# INH_v4_01.net
KiCad netlist of a schematic drawn in Altium Designer
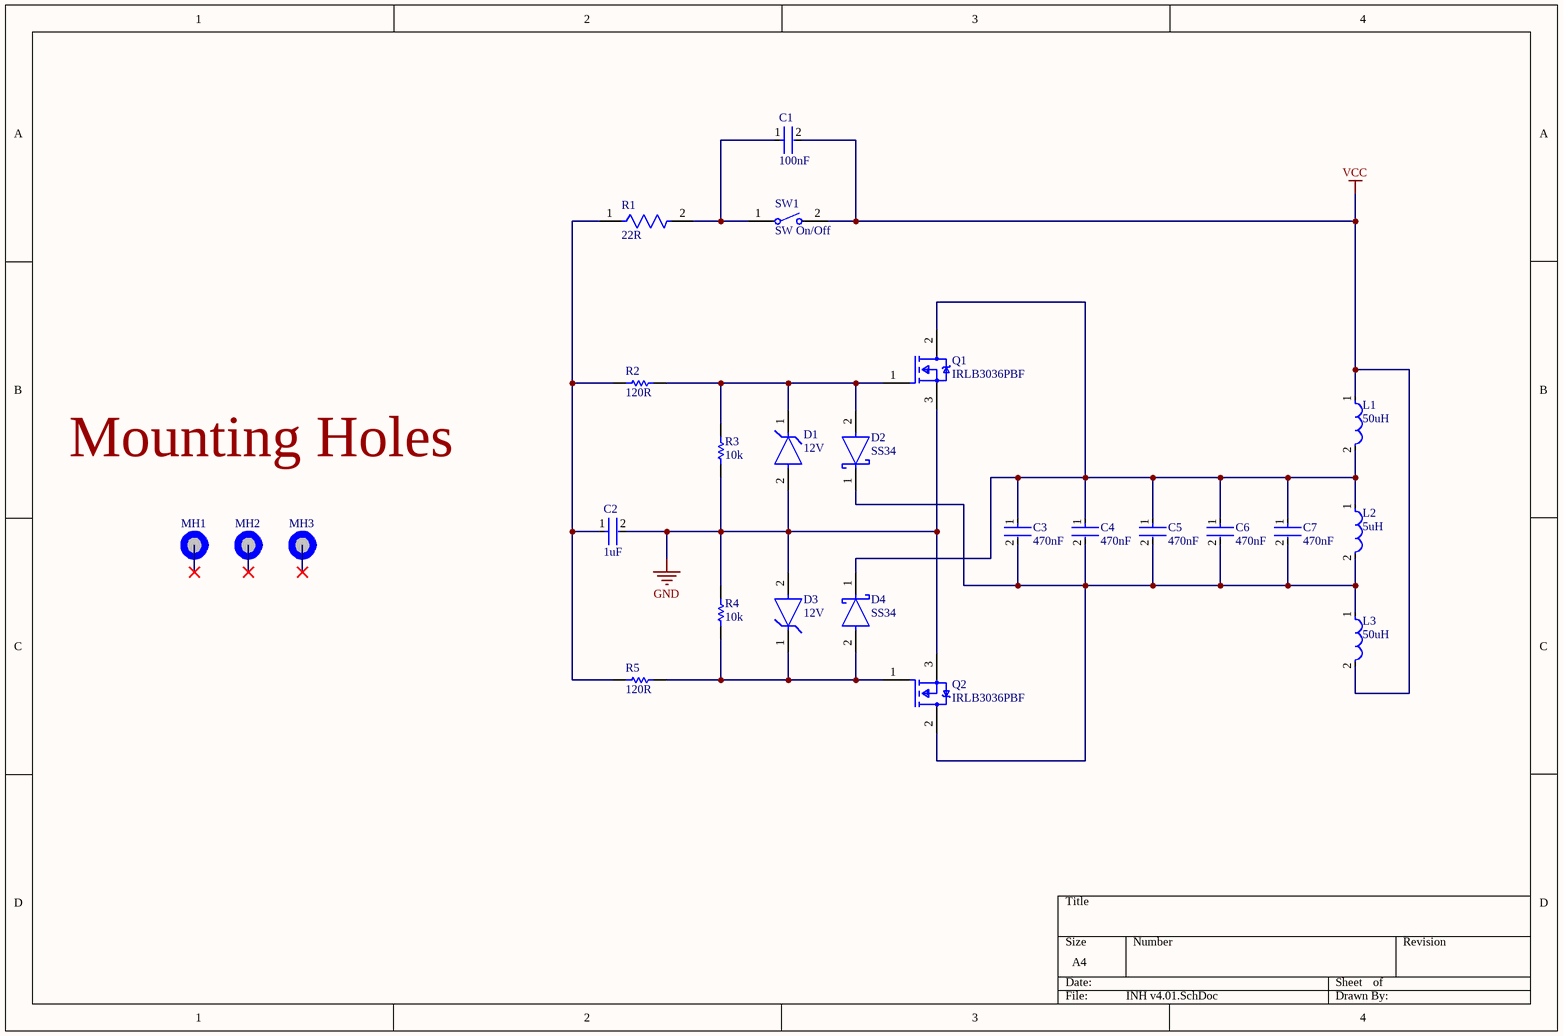
[diagram p0: INH v4.01.SchDoc]

(export (version "E")
  (design (tool "Eeschema 10.0.6"))
  (components
    (comp (ref "C1")
      (value "100nF")
      (footprint "1206 Capacitor")
      (libsource (lib "INH v4.01") (part "C 1206 100nF"))
    )
    (comp (ref "C2")
      (value "1uF")
      (footprint "1206 Capacitor")
      (description "Cap Ceramic 1uF 25V X7R ±20% SMD 1206 +125°C Embossed T/R")
      (fields (field (name "TOLERANCE") "20%"))
      (libsource (lib "INH v4.01") (part "C 1206 1uF"))
    )
    (comp (ref "C3")
      (value "470nF")
      (footprint "THT Capacitor P15mm (84x183mm)")
      (description "PP X2 Capacitor 470nF 275V")
      (libsource (lib "INH v4.01") (part "C 084x183 P15 470nF"))
    )
    (comp (ref "C4")
      (value "470nF")
      (footprint "THT Capacitor P15mm (84x183mm)")
      (description "PP X2 Capacitor 470nF 275V")
      (libsource (lib "INH v4.01") (part "C 084x183 P15 470nF"))
    )
    (comp (ref "C5")
      (value "470nF")
      (footprint "THT Capacitor P15mm (84x183mm)")
      (description "PP X2 Capacitor 470nF 275V")
      (libsource (lib "INH v4.01") (part "C 084x183 P15 470nF"))
    )
    (comp (ref "C6")
      (value "470nF")
      (footprint "THT Capacitor P15mm (84x183mm)")
      (description "PP X2 Capacitor 470nF 275V")
      (libsource (lib "INH v4.01") (part "C 084x183 P15 470nF"))
    )
    (comp (ref "C7")
      (value "470nF")
      (footprint "THT Capacitor P15mm (84x183mm)")
      (description "PP X2 Capacitor 470nF 275V")
      (libsource (lib "INH v4.01") (part "C 084x183 P15 470nF"))
    )
    (comp (ref "D1")
      (value "12V")
      (footprint "DO-41")
      (description "BZX85C10-T50R Zener Diode, 12V V(Z), 2%, 1W, Silicon, Unidirectional, DO-41")
      (fields (field (name "TOLERANCE") "5%"))
      (libsource (lib "INH v4.01") (part "DZ DO-41 12v"))
    )
    (comp (ref "D2")
      (value "SS34")
      (footprint "DO-214")
      (description "DIODE SCHOTTKY 40V 3A DO214AB")
      (fields (field (name "MANUFACTURER") "Vishay") (field (name "MANUFACTURER PART NUMBER") "SS34-E3/57T"))
      (libsource (lib "INH v4.01") (part "D DO-214 Schottky"))
    )
    (comp (ref "D3")
      (value "12V")
      (footprint "DO-41")
      (description "BZX85C10-T50R Zener Diode, 12V V(Z), 2%, 1W, Silicon, Unidirectional, DO-41")
      (fields (field (name "TOLERANCE") "5%"))
      (libsource (lib "INH v4.01") (part "DZ DO-41 12v"))
    )
    (comp (ref "D4")
      (value "SS34")
      (footprint "DO-214")
      (description "DIODE SCHOTTKY 40V 3A DO214AB")
      (fields (field (name "MANUFACTURER") "Vishay") (field (name "MANUFACTURER PART NUMBER") "SS34-E3/57T"))
      (libsource (lib "INH v4.01") (part "D DO-214 Schottky"))
    )
    (comp (ref "L1") (value "50uH") (footprint "L 50uh") (libsource (lib "INH v4.01") (part "L 50uH")))
    (comp (ref "L2") (value "5uH") (footprint "L Main") (libsource (lib "INH v4.01") (part "L Main")))
    (comp (ref "L3") (value "50uH") (footprint "L 50uh") (libsource (lib "INH v4.01") (part "L 50uH")))
    (comp (ref "MH1")
      (value "Mounting Hole m3")
      (footprint "Mounting Hole m3")
      (libsource (lib "INH v4.01") (part "Mounting Hole m3"))
    )
    (comp (ref "MH2")
      (value "Mounting Hole m3")
      (footprint "Mounting Hole m3")
      (libsource (lib "INH v4.01") (part "Mounting Hole m3"))
    )
    (comp (ref "MH3")
      (value "Mounting Hole m3")
      (footprint "Mounting Hole m3")
      (libsource (lib "INH v4.01") (part "Mounting Hole m3"))
    )
    (comp (ref "Q1")
      (value "IRLB3036PBF")
      (footprint "FP-PG-TO220-3-MFG")
      (description "MOSFET N-CH 60V 195A TO220AB")
      (libsource (lib "INH v4.01") (part "Q TO-220 IRLB3036PBF"))
    )
    (comp (ref "Q2")
      (value "IRLB3036PBF")
      (footprint "FP-PG-TO220-3-MFG")
      (description "MOSFET N-CH 60V 195A TO220AB")
      (libsource (lib "INH v4.01") (part "Q TO-220 IRLB3036PBF"))
    )
    (comp (ref "R1")
      (value "22R")
      (footprint "FP-CRCW2512-e3-MFG")
      (description "RES Thick Film, 22Ω, 5%, 1W, 200ppm/°C, 2512")
      (fields (field (name "TOLERANCE") "5%"))
      (libsource (lib "Altium Content Vault") (part "1029c3af85768c4190bb7ad29bc67b5"))
    )
    (comp (ref "R2")
      (value "120R")
      (footprint "RESC2013X60X40ML20T25")
      (fields (field (name "MANUFACTURER") "Panasonic") (field (name "PART NUMBER") "ERA6AEB121V"))
      (libsource (lib "Altium Content Vault") (part "RES"))
    )
    (comp (ref "R3")
      (value "10k")
      (footprint "RESC2013X60X35ML10T20")
      (description "Chip Resistor, 10 KOhm, +/- 1%, 0.125 W, -55 to 155 degC, 0805 (2012 Metric), RoHS, Tape and Reel")
      (fields (field (name "MANUFACTURER") "Yageo"))
      (libsource (lib "Altium Content Vault") (part "RES-2"))
    )
    (comp (ref "R4")
      (value "10k")
      (footprint "RESC2013X60X35ML10T20")
      (description "Chip Resistor, 10 KOhm, +/- 1%, 0.125 W, -55 to 155 degC, 0805 (2012 Metric), RoHS, Tape and Reel")
      (fields (field (name "MANUFACTURER") "Yageo"))
      (libsource (lib "Altium Content Vault") (part "RES-2"))
    )
    (comp (ref "R5")
      (value "120R")
      (footprint "RESC2013X60X40ML20T25")
      (fields (field (name "MANUFACTURER") "Panasonic") (field (name "PART NUMBER") "ERA6AEB121V"))
      (libsource (lib "Altium Content Vault") (part "RES"))
    )
    (comp (ref "SW1")
      (value "SW On/Off")
      (footprint "SW On/Off")
      (description "Push Button Switch")
      (fields (field (name "MANUFACTURER") "TE Connectivity"))
      (libsource (lib "INH v4.01") (part "SW On/Off"))
    )
  )
  (nets
    (net (code "1") (name "GND") (class "Default")
      (node (ref "C2") (pin "2") (pinfunction "2_2") (pintype "passive"))
      (node (ref "D1") (pin "2") (pinfunction "A_2") (pintype "passive"))
      (node (ref "D3") (pin "2") (pinfunction "A_2") (pintype "passive"))
      (node (ref "Q1") (pin "3") (pinfunction "SOURCE_3") (pintype "passive"))
      (node (ref "Q2") (pin "3") (pinfunction "SOURCE_3") (pintype "passive"))
      (node (ref "R3") (pin "1") (pinfunction "1_1") (pintype "passive"))
      (node (ref "R4") (pin "2") (pinfunction "2_2") (pintype "passive"))
    )
    (net (code "2") (name "Net-(C1-Pad1)") (class "Default")
      (node (ref "C1") (pin "1") (pinfunction "1_1") (pintype "passive"))
      (node (ref "R1") (pin "2") (pinfunction "2_2") (pintype "passive"))
      (node (ref "SW1") (pin "1") (pinfunction "1_1") (pintype "passive"))
    )
    (net (code "3") (name "Net-(C2-Pad1)") (class "Default")
      (node (ref "C2") (pin "1") (pinfunction "1_1") (pintype "passive"))
      (node (ref "R1") (pin "1") (pinfunction "1_1") (pintype "passive"))
      (node (ref "R2") (pin "1") (pinfunction "1_1") (pintype "passive"))
      (node (ref "R5") (pin "1") (pinfunction "1_1") (pintype "passive"))
    )
    (net (code "4") (name "Net-(D1-C)") (class "Default")
      (node (ref "D1") (pin "1") (pinfunction "C_1") (pintype "passive"))
      (node (ref "D2") (pin "2") (pinfunction "A_2") (pintype "passive"))
      (node (ref "Q1") (pin "1") (pinfunction "GATE_1") (pintype "passive"))
      (node (ref "R2") (pin "2") (pinfunction "2_2") (pintype "passive"))
      (node (ref "R3") (pin "2") (pinfunction "2_2") (pintype "passive"))
    )
    (net (code "5") (name "Net-(D2-C)") (class "Default")
      (node (ref "C3") (pin "2") (pinfunction "2_2") (pintype "passive"))
      (node (ref "C4") (pin "2") (pinfunction "2_2") (pintype "passive"))
      (node (ref "C5") (pin "2") (pinfunction "2_2") (pintype "passive"))
      (node (ref "C6") (pin "2") (pinfunction "2_2") (pintype "passive"))
      (node (ref "C7") (pin "2") (pinfunction "2_2") (pintype "passive"))
      (node (ref "D2") (pin "1") (pinfunction "C_1") (pintype "passive"))
      (node (ref "L2") (pin "2") (pinfunction "2_2") (pintype "passive"))
      (node (ref "L3") (pin "1") (pinfunction "1_1") (pintype "passive"))
      (node (ref "Q2") (pin "2") (pinfunction "DRAIN_2") (pintype "passive"))
    )
    (net (code "6") (name "Net-(D3-C)") (class "Default")
      (node (ref "D3") (pin "1") (pinfunction "C_1") (pintype "passive"))
      (node (ref "D4") (pin "2") (pinfunction "A_2") (pintype "passive"))
      (node (ref "Q2") (pin "1") (pinfunction "GATE_1") (pintype "passive"))
      (node (ref "R4") (pin "1") (pinfunction "1_1") (pintype "passive"))
      (node (ref "R5") (pin "2") (pinfunction "2_2") (pintype "passive"))
    )
    (net (code "7") (name "Net-(D4-C)") (class "Default")
      (node (ref "C3") (pin "1") (pinfunction "1_1") (pintype "passive"))
      (node (ref "C4") (pin "1") (pinfunction "1_1") (pintype "passive"))
      (node (ref "C5") (pin "1") (pinfunction "1_1") (pintype "passive"))
      (node (ref "C6") (pin "1") (pinfunction "1_1") (pintype "passive"))
      (node (ref "C7") (pin "1") (pinfunction "1_1") (pintype "passive"))
      (node (ref "D4") (pin "1") (pinfunction "C_1") (pintype "passive"))
      (node (ref "L1") (pin "2") (pinfunction "2_2") (pintype "passive"))
      (node (ref "L2") (pin "1") (pinfunction "1_1") (pintype "passive"))
      (node (ref "Q1") (pin "2") (pinfunction "DRAIN_2") (pintype "passive"))
    )
    (net (code "8") (name "VCC") (class "Default")
      (node (ref "C1") (pin "2") (pinfunction "2_2") (pintype "passive"))
      (node (ref "L1") (pin "1") (pinfunction "1_1") (pintype "passive"))
      (node (ref "L3") (pin "2") (pinfunction "2_2") (pintype "passive"))
      (node (ref "SW1") (pin "2") (pinfunction "2_2") (pintype "passive"))
    )
  )
)
